# BLDC-sensorless-prototip-1.net
KiCad netlist of a schematic drawn in Altium Designer
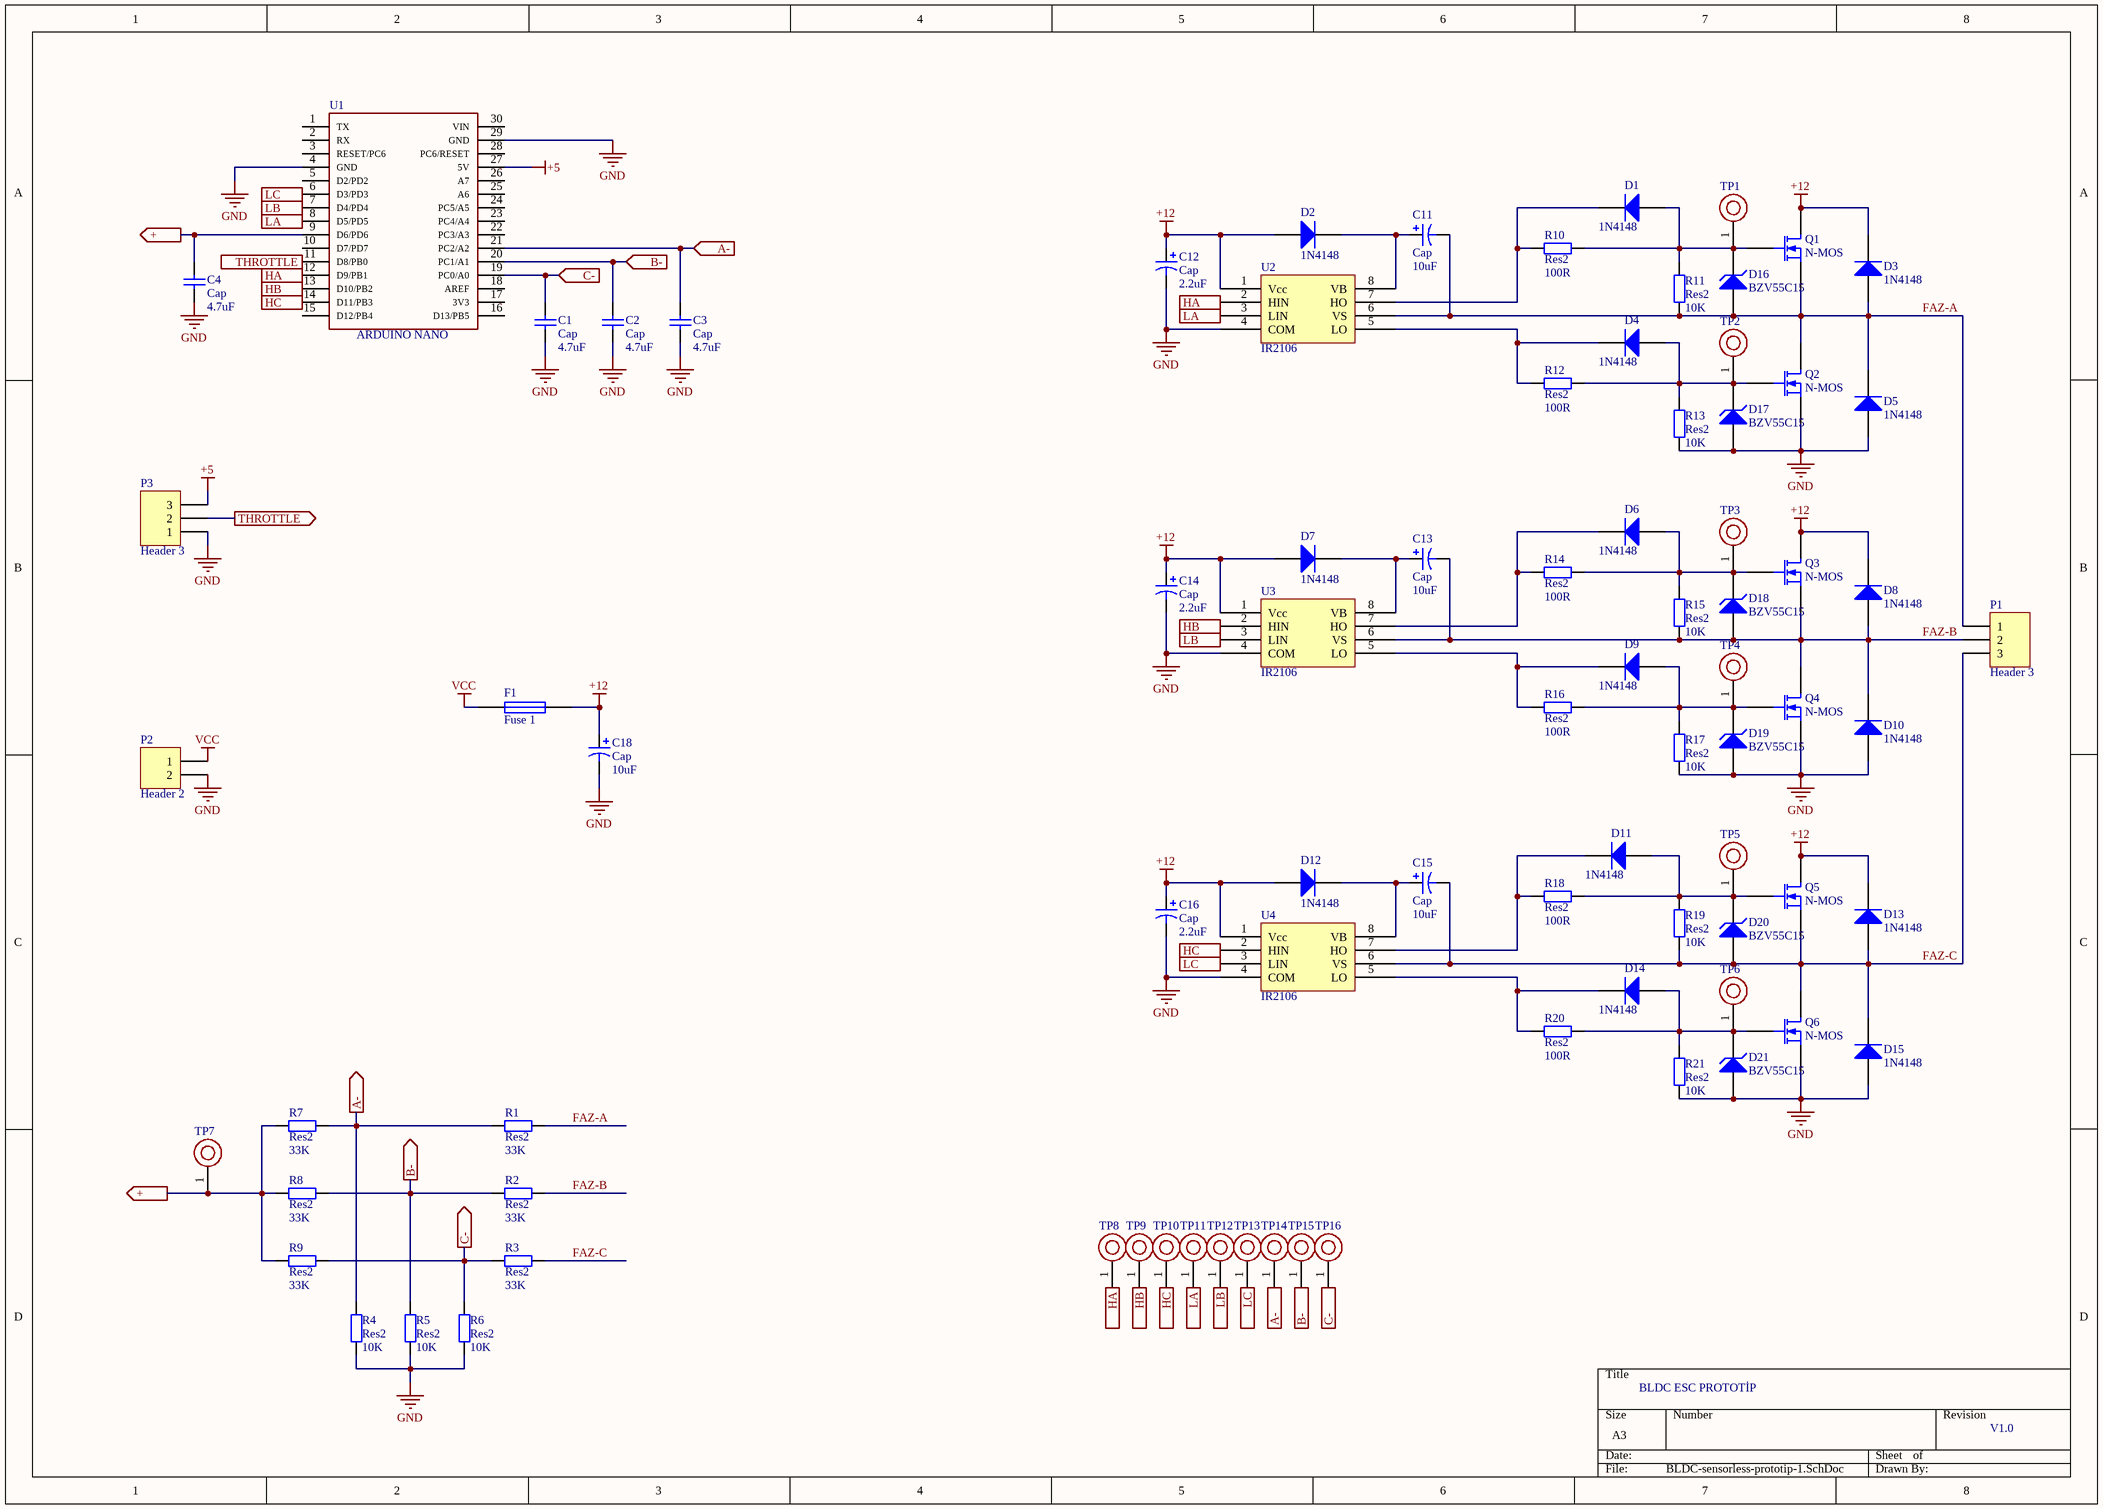
[diagram p0: BLDC-sensorless-prototip-1.SchDoc]

(export (version "E")
  (design (tool "Eeschema 10.0.6"))
  (components
    (comp (ref "C1")
      (value "Cap")
      (footprint "CAP-1206")
      (description "Capacitor")
      (fields (field (name "ALTIUM_VALUE") "4.7uF") (field (name "PUBLISHER") "Altium Limited"))
      (libsource (lib "Miscellaneous Devices") (part "Cap"))
    )
    (comp (ref "C2")
      (value "Cap")
      (footprint "CAP-1206")
      (description "Capacitor")
      (fields (field (name "ALTIUM_VALUE") "4.7uF") (field (name "PUBLISHER") "Altium Limited"))
      (libsource (lib "Miscellaneous Devices") (part "Cap"))
    )
    (comp (ref "C3")
      (value "Cap")
      (footprint "CAP-1206")
      (description "Capacitor")
      (fields (field (name "ALTIUM_VALUE") "4.7uF") (field (name "PUBLISHER") "Altium Limited"))
      (libsource (lib "Miscellaneous Devices") (part "Cap"))
    )
    (comp (ref "C4")
      (value "Cap")
      (footprint "CAP-1206")
      (description "Capacitor")
      (fields (field (name "ALTIUM_VALUE") "4.7uF") (field (name "PUBLISHER") "Altium Limited"))
      (libsource (lib "Miscellaneous Devices") (part "Cap"))
    )
    (comp (ref "C11")
      (value "Cap")
      (footprint "CAP-ELEC-2.54MM")
      (description "Polarized Capacitor (Radial)")
      (fields (field (name "ALTIUM_VALUE") "10uF") (field (name "PUBLISHER") "Altium Limited"))
      (libsource (lib "Miscellaneous Devices") (part "Cap Pol1"))
    )
    (comp (ref "C12")
      (value "Cap")
      (footprint "CAP-ELEC-2.54MM")
      (description "Polarized Capacitor (Radial)")
      (fields (field (name "ALTIUM_VALUE") "2.2uF") (field (name "PUBLISHER") "Altium Limited"))
      (libsource (lib "Miscellaneous Devices") (part "Cap Pol1"))
    )
    (comp (ref "C13")
      (value "Cap")
      (footprint "CAP-ELEC-2.54MM")
      (description "Polarized Capacitor (Radial)")
      (fields (field (name "ALTIUM_VALUE") "10uF") (field (name "PUBLISHER") "Altium Limited"))
      (libsource (lib "Miscellaneous Devices") (part "Cap Pol1"))
    )
    (comp (ref "C14")
      (value "Cap")
      (footprint "CAP-ELEC-2.54MM")
      (description "Polarized Capacitor (Radial)")
      (fields (field (name "ALTIUM_VALUE") "2.2uF") (field (name "PUBLISHER") "Altium Limited"))
      (libsource (lib "Miscellaneous Devices") (part "Cap Pol1"))
    )
    (comp (ref "C15")
      (value "Cap")
      (footprint "CAP-ELEC-2.54MM")
      (description "Polarized Capacitor (Radial)")
      (fields (field (name "ALTIUM_VALUE") "10uF") (field (name "PUBLISHER") "Altium Limited"))
      (libsource (lib "Miscellaneous Devices") (part "Cap Pol1"))
    )
    (comp (ref "C16")
      (value "Cap")
      (footprint "CAP-ELEC-2.54MM")
      (description "Polarized Capacitor (Radial)")
      (fields (field (name "ALTIUM_VALUE") "2.2uF") (field (name "PUBLISHER") "Altium Limited"))
      (libsource (lib "Miscellaneous Devices") (part "Cap Pol1"))
    )
    (comp (ref "C18")
      (value "Cap")
      (footprint "CAP-ELEC-2.54MM")
      (description "Polarized Capacitor (Radial)")
      (fields (field (name "ALTIUM_VALUE") "10uF") (field (name "PUBLISHER") "Altium Limited"))
      (libsource (lib "Miscellaneous Devices") (part "Cap Pol1"))
    )
    (comp (ref "D1")
      (value "1N4148")
      (footprint "DO-213-minielf (SOD80)")
      (description "High Conductance Fast Diode")
      (fields (field (name "PUBLISHER") "Altium Limited"))
      (libsource (lib "Miscellaneous Devices") (part "Diode 1N4148"))
    )
    (comp (ref "D2")
      (value "1N4148")
      (footprint "DO-213-minielf (SOD80)")
      (description "High Conductance Fast Diode")
      (fields (field (name "PUBLISHER") "Altium Limited"))
      (libsource (lib "Miscellaneous Devices") (part "Diode 1N4148"))
    )
    (comp (ref "D3")
      (value "1N4148")
      (footprint "DO-213-minielf (SOD80)")
      (description "Default Diode")
      (fields (field (name "PUBLISHER") "Altium Limited"))
      (libsource (lib "Miscellaneous Devices") (part "Diode"))
    )
    (comp (ref "D4")
      (value "1N4148")
      (footprint "DO-213-minielf (SOD80)")
      (description "High Conductance Fast Diode")
      (fields (field (name "PUBLISHER") "Altium Limited"))
      (libsource (lib "Miscellaneous Devices") (part "Diode 1N4148"))
    )
    (comp (ref "D5")
      (value "1N4148")
      (footprint "DO-213-minielf (SOD80)")
      (description "Default Diode")
      (fields (field (name "PUBLISHER") "Altium Limited"))
      (libsource (lib "Miscellaneous Devices") (part "Diode"))
    )
    (comp (ref "D6")
      (value "1N4148")
      (footprint "DO-213-minielf (SOD80)")
      (description "High Conductance Fast Diode")
      (fields (field (name "PUBLISHER") "Altium Limited"))
      (libsource (lib "Miscellaneous Devices") (part "Diode 1N4148"))
    )
    (comp (ref "D7")
      (value "1N4148")
      (footprint "DO-213-minielf (SOD80)")
      (description "High Conductance Fast Diode")
      (fields (field (name "PUBLISHER") "Altium Limited"))
      (libsource (lib "Miscellaneous Devices") (part "Diode 1N4148"))
    )
    (comp (ref "D8")
      (value "1N4148")
      (footprint "DO-213-minielf (SOD80)")
      (description "Default Diode")
      (fields (field (name "PUBLISHER") "Altium Limited"))
      (libsource (lib "Miscellaneous Devices") (part "Diode"))
    )
    (comp (ref "D9")
      (value "1N4148")
      (footprint "DO-213-minielf (SOD80)")
      (description "High Conductance Fast Diode")
      (fields (field (name "PUBLISHER") "Altium Limited"))
      (libsource (lib "Miscellaneous Devices") (part "Diode 1N4148"))
    )
    (comp (ref "D10")
      (value "1N4148")
      (footprint "DO-213-minielf (SOD80)")
      (description "Default Diode")
      (fields (field (name "PUBLISHER") "Altium Limited"))
      (libsource (lib "Miscellaneous Devices") (part "Diode"))
    )
    (comp (ref "D11")
      (value "1N4148")
      (footprint "DO-213-minielf (SOD80)")
      (description "High Conductance Fast Diode")
      (fields (field (name "PUBLISHER") "Altium Limited"))
      (libsource (lib "Miscellaneous Devices") (part "Diode 1N4148"))
    )
    (comp (ref "D12")
      (value "1N4148")
      (footprint "DO-213-minielf (SOD80)")
      (description "High Conductance Fast Diode")
      (fields (field (name "PUBLISHER") "Altium Limited"))
      (libsource (lib "Miscellaneous Devices") (part "Diode 1N4148"))
    )
    (comp (ref "D13")
      (value "1N4148")
      (footprint "DO-213-minielf (SOD80)")
      (description "Default Diode")
      (fields (field (name "PUBLISHER") "Altium Limited"))
      (libsource (lib "Miscellaneous Devices") (part "Diode"))
    )
    (comp (ref "D14")
      (value "1N4148")
      (footprint "DO-213-minielf (SOD80)")
      (description "High Conductance Fast Diode")
      (fields (field (name "PUBLISHER") "Altium Limited"))
      (libsource (lib "Miscellaneous Devices") (part "Diode 1N4148"))
    )
    (comp (ref "D15")
      (value "1N4148")
      (footprint "DO-213-minielf (SOD80)")
      (description "Default Diode")
      (fields (field (name "PUBLISHER") "Altium Limited"))
      (libsource (lib "Miscellaneous Devices") (part "Diode"))
    )
    (comp (ref "D16")
      (value "BZV55C15")
      (footprint "DO-213-minielf (SOD80)")
      (description "Zener Diode")
      (fields (field (name "PUBLISHER") "Altium Limited"))
      (libsource (lib "Miscellaneous Devices") (part "D Zener"))
    )
    (comp (ref "D17")
      (value "BZV55C15")
      (footprint "DO-213-minielf (SOD80)")
      (description "Zener Diode")
      (fields (field (name "PUBLISHER") "Altium Limited"))
      (libsource (lib "Miscellaneous Devices") (part "D Zener"))
    )
    (comp (ref "D18")
      (value "BZV55C15")
      (footprint "DO-213-minielf (SOD80)")
      (description "Zener Diode")
      (fields (field (name "PUBLISHER") "Altium Limited"))
      (libsource (lib "Miscellaneous Devices") (part "D Zener"))
    )
    (comp (ref "D19")
      (value "BZV55C15")
      (footprint "DO-213-minielf (SOD80)")
      (description "Zener Diode")
      (fields (field (name "PUBLISHER") "Altium Limited"))
      (libsource (lib "Miscellaneous Devices") (part "D Zener"))
    )
    (comp (ref "D20")
      (value "BZV55C15")
      (footprint "DO-213-minielf (SOD80)")
      (description "Zener Diode")
      (fields (field (name "PUBLISHER") "Altium Limited"))
      (libsource (lib "Miscellaneous Devices") (part "D Zener"))
    )
    (comp (ref "D21")
      (value "BZV55C15")
      (footprint "DO-213-minielf (SOD80)")
      (description "Zener Diode")
      (fields (field (name "PUBLISHER") "Altium Limited"))
      (libsource (lib "Miscellaneous Devices") (part "D Zener"))
    )
    (comp (ref "F1")
      (value "Fuse 1")
      (footprint "FUSE HOLDER")
      (description "Fuse")
      (fields (field (name "PUBLISHER") "Altium Limited"))
      (libsource (lib "Miscellaneous Devices") (part "Fuse 1"))
    )
    (comp (ref "P1")
      (value "Header 3")
      (footprint "3.81MM KLEMENS X3")
      (description "Header, 3-Pin")
      (fields (field (name "PUBLISHER") "Altium Limited"))
      (libsource (lib "") (part "Header 3_1"))
    )
    (comp (ref "P2")
      (value "Header 2")
      (footprint "5.08MM KLEMENS X2")
      (description "Header, 2-Pin")
      (fields (field (name "PUBLISHER") "Altium Limited"))
      (libsource (lib "Miscellaneous Connectors") (part "Header 2"))
    )
    (comp (ref "P3")
      (value "Header 3")
      (footprint "2.54MM ERKEK HEADER X3")
      (description "Header, 3-Pin")
      (fields (field (name "PUBLISHER") "Altium Limited"))
      (libsource (lib "Miscellaneous Connectors") (part "Header 3"))
    )
    (comp (ref "Q1")
      (value "N-MOS")
      (footprint "TO-252-3")
      (description "N-Channel MOSFET")
      (fields (field (name "PUBLISHER") "Altium Limited"))
      (libsource (lib "Miscellaneous Devices") (part "MOSFET-N"))
    )
    (comp (ref "Q2")
      (value "N-MOS")
      (footprint "TO-252-3")
      (description "N-Channel MOSFET")
      (fields (field (name "PUBLISHER") "Altium Limited"))
      (libsource (lib "Miscellaneous Devices") (part "MOSFET-N"))
    )
    (comp (ref "Q3")
      (value "N-MOS")
      (footprint "TO-252-3")
      (description "N-Channel MOSFET")
      (fields (field (name "PUBLISHER") "Altium Limited"))
      (libsource (lib "Miscellaneous Devices") (part "MOSFET-N"))
    )
    (comp (ref "Q4")
      (value "N-MOS")
      (footprint "TO-252-3")
      (description "N-Channel MOSFET")
      (fields (field (name "PUBLISHER") "Altium Limited"))
      (libsource (lib "Miscellaneous Devices") (part "MOSFET-N"))
    )
    (comp (ref "Q5")
      (value "N-MOS")
      (footprint "TO-252-3")
      (description "N-Channel MOSFET")
      (fields (field (name "PUBLISHER") "Altium Limited"))
      (libsource (lib "Miscellaneous Devices") (part "MOSFET-N"))
    )
    (comp (ref "Q6")
      (value "N-MOS")
      (footprint "TO-252-3")
      (description "N-Channel MOSFET")
      (fields (field (name "PUBLISHER") "Altium Limited"))
      (libsource (lib "Miscellaneous Devices") (part "MOSFET-N"))
    )
    (comp (ref "R1")
      (value "Res2")
      (footprint "RES-1206")
      (description "Resistor")
      (fields (field (name "ALTIUM_VALUE") "33K") (field (name "PUBLISHER") "Altium Limited"))
      (libsource (lib "Miscellaneous Devices") (part "Res2"))
    )
    (comp (ref "R2")
      (value "Res2")
      (footprint "RES-1206")
      (description "Resistor")
      (fields (field (name "ALTIUM_VALUE") "33K") (field (name "PUBLISHER") "Altium Limited"))
      (libsource (lib "Miscellaneous Devices") (part "Res2"))
    )
    (comp (ref "R3")
      (value "Res2")
      (footprint "RES-1206")
      (description "Resistor")
      (fields (field (name "ALTIUM_VALUE") "33K") (field (name "PUBLISHER") "Altium Limited"))
      (libsource (lib "Miscellaneous Devices") (part "Res2"))
    )
    (comp (ref "R4")
      (value "Res2")
      (footprint "RES-1206")
      (description "Resistor")
      (fields (field (name "ALTIUM_VALUE") "10K") (field (name "PUBLISHER") "Altium Limited"))
      (libsource (lib "") (part "Res2_1"))
    )
    (comp (ref "R5")
      (value "Res2")
      (footprint "RES-1206")
      (description "Resistor")
      (fields (field (name "ALTIUM_VALUE") "10K") (field (name "PUBLISHER") "Altium Limited"))
      (libsource (lib "") (part "Res2_1"))
    )
    (comp (ref "R6")
      (value "Res2")
      (footprint "RES-1206")
      (description "Resistor")
      (fields (field (name "ALTIUM_VALUE") "10K") (field (name "PUBLISHER") "Altium Limited"))
      (libsource (lib "") (part "Res2_1"))
    )
    (comp (ref "R7")
      (value "Res2")
      (footprint "RES-1206")
      (description "Resistor")
      (fields (field (name "ALTIUM_VALUE") "33K") (field (name "PUBLISHER") "Altium Limited"))
      (libsource (lib "Miscellaneous Devices") (part "Res2"))
    )
    (comp (ref "R8")
      (value "Res2")
      (footprint "RES-1206")
      (description "Resistor")
      (fields (field (name "ALTIUM_VALUE") "33K") (field (name "PUBLISHER") "Altium Limited"))
      (libsource (lib "Miscellaneous Devices") (part "Res2"))
    )
    (comp (ref "R9")
      (value "Res2")
      (footprint "RES-1206")
      (description "Resistor")
      (fields (field (name "ALTIUM_VALUE") "33K") (field (name "PUBLISHER") "Altium Limited"))
      (libsource (lib "Miscellaneous Devices") (part "Res2"))
    )
    (comp (ref "R10")
      (value "Res2")
      (footprint "RES-1206")
      (description "Resistor")
      (fields (field (name "ALTIUM_VALUE") "100R") (field (name "PUBLISHER") "Altium Limited"))
      (libsource (lib "Miscellaneous Devices") (part "Res2"))
    )
    (comp (ref "R11")
      (value "Res2")
      (footprint "RES-1206")
      (description "Resistor")
      (fields (field (name "ALTIUM_VALUE") "10K") (field (name "PUBLISHER") "Altium Limited"))
      (libsource (lib "") (part "Res2_1"))
    )
    (comp (ref "R12")
      (value "Res2")
      (footprint "RES-1206")
      (description "Resistor")
      (fields (field (name "ALTIUM_VALUE") "100R") (field (name "PUBLISHER") "Altium Limited"))
      (libsource (lib "Miscellaneous Devices") (part "Res2"))
    )
    (comp (ref "R13")
      (value "Res2")
      (footprint "RES-1206")
      (description "Resistor")
      (fields (field (name "ALTIUM_VALUE") "10K") (field (name "PUBLISHER") "Altium Limited"))
      (libsource (lib "") (part "Res2_1"))
    )
    (comp (ref "R14")
      (value "Res2")
      (footprint "RES-1206")
      (description "Resistor")
      (fields (field (name "ALTIUM_VALUE") "100R") (field (name "PUBLISHER") "Altium Limited"))
      (libsource (lib "Miscellaneous Devices") (part "Res2"))
    )
    (comp (ref "R15")
      (value "Res2")
      (footprint "RES-1206")
      (description "Resistor")
      (fields (field (name "ALTIUM_VALUE") "10K") (field (name "PUBLISHER") "Altium Limited"))
      (libsource (lib "") (part "Res2_1"))
    )
    (comp (ref "R16")
      (value "Res2")
      (footprint "RES-1206")
      (description "Resistor")
      (fields (field (name "ALTIUM_VALUE") "100R") (field (name "PUBLISHER") "Altium Limited"))
      (libsource (lib "Miscellaneous Devices") (part "Res2"))
    )
    (comp (ref "R17")
      (value "Res2")
      (footprint "RES-1206")
      (description "Resistor")
      (fields (field (name "ALTIUM_VALUE") "10K") (field (name "PUBLISHER") "Altium Limited"))
      (libsource (lib "") (part "Res2_1"))
    )
    (comp (ref "R18")
      (value "Res2")
      (footprint "RES-1206")
      (description "Resistor")
      (fields (field (name "ALTIUM_VALUE") "100R") (field (name "PUBLISHER") "Altium Limited"))
      (libsource (lib "Miscellaneous Devices") (part "Res2"))
    )
    (comp (ref "R19")
      (value "Res2")
      (footprint "RES-1206")
      (description "Resistor")
      (fields (field (name "ALTIUM_VALUE") "10K") (field (name "PUBLISHER") "Altium Limited"))
      (libsource (lib "") (part "Res2_1"))
    )
    (comp (ref "R20")
      (value "Res2")
      (footprint "RES-1206")
      (description "Resistor")
      (fields (field (name "ALTIUM_VALUE") "100R") (field (name "PUBLISHER") "Altium Limited"))
      (libsource (lib "Miscellaneous Devices") (part "Res2"))
    )
    (comp (ref "R21")
      (value "Res2")
      (footprint "RES-1206")
      (description "Resistor")
      (fields (field (name "ALTIUM_VALUE") "10K") (field (name "PUBLISHER") "Altium Limited"))
      (libsource (lib "") (part "Res2_1"))
    )
    (comp (ref "TP1")
      (value "TEST POINT")
      (footprint "Test Point")
      (libsource (lib "Sematik Kutuphane") (part "TEST POINT"))
    )
    (comp (ref "TP2")
      (value "TEST POINT")
      (footprint "Test Point")
      (libsource (lib "Sematik Kutuphane") (part "TEST POINT"))
    )
    (comp (ref "TP3")
      (value "TEST POINT")
      (footprint "Test Point")
      (libsource (lib "Sematik Kutuphane") (part "TEST POINT"))
    )
    (comp (ref "TP4")
      (value "TEST POINT")
      (footprint "Test Point")
      (libsource (lib "Sematik Kutuphane") (part "TEST POINT"))
    )
    (comp (ref "TP5")
      (value "TEST POINT")
      (footprint "Test Point")
      (libsource (lib "Sematik Kutuphane") (part "TEST POINT"))
    )
    (comp (ref "TP6")
      (value "TEST POINT")
      (footprint "Test Point")
      (libsource (lib "Sematik Kutuphane") (part "TEST POINT"))
    )
    (comp (ref "TP7")
      (value "TEST POINT")
      (footprint "Test Point")
      (libsource (lib "Sematik Kutuphane") (part "TEST POINT"))
    )
    (comp (ref "TP8")
      (value "TEST POINT")
      (footprint "Test Point")
      (libsource (lib "Sematik Kutuphane") (part "TEST POINT"))
    )
    (comp (ref "TP9")
      (value "TEST POINT")
      (footprint "Test Point")
      (libsource (lib "Sematik Kutuphane") (part "TEST POINT"))
    )
    (comp (ref "TP10")
      (value "TEST POINT")
      (footprint "Test Point")
      (libsource (lib "Sematik Kutuphane") (part "TEST POINT"))
    )
    (comp (ref "TP11")
      (value "TEST POINT")
      (footprint "Test Point")
      (libsource (lib "Sematik Kutuphane") (part "TEST POINT"))
    )
    (comp (ref "TP12")
      (value "TEST POINT")
      (footprint "Test Point")
      (libsource (lib "Sematik Kutuphane") (part "TEST POINT"))
    )
    (comp (ref "TP13")
      (value "TEST POINT")
      (footprint "Test Point")
      (libsource (lib "Sematik Kutuphane") (part "TEST POINT"))
    )
    (comp (ref "TP14")
      (value "TEST POINT")
      (footprint "Test Point")
      (libsource (lib "Sematik Kutuphane") (part "TEST POINT"))
    )
    (comp (ref "TP15")
      (value "TEST POINT")
      (footprint "Test Point")
      (libsource (lib "Sematik Kutuphane") (part "TEST POINT"))
    )
    (comp (ref "TP16")
      (value "TEST POINT")
      (footprint "Test Point")
      (libsource (lib "Sematik Kutuphane") (part "TEST POINT"))
    )
    (comp (ref "U1")
      (value "ARDUINO NANO")
      (footprint "ARDUINO NANO")
      (libsource (lib "Sematik Kutuphane") (part "ARDUINO NANO"))
    )
    (comp (ref "U2")
      (value "IR2106")
      (footprint "DIP-8")
      (libsource (lib "Sematik Kutuphane") (part "IR2106"))
    )
    (comp (ref "U3")
      (value "IR2106")
      (footprint "DIP-8")
      (libsource (lib "Sematik Kutuphane") (part "IR2106"))
    )
    (comp (ref "U4")
      (value "IR2106")
      (footprint "DIP-8")
      (libsource (lib "Sematik Kutuphane") (part "IR2106"))
    )
  )
  (nets
    (net (code "1") (name "+5") (class "Default")
      (node (ref "P3") (pin "3") (pinfunction "3_3") (pintype "passive"))
      (node (ref "U1") (pin "27") (pinfunction "5V_27") (pintype "passive"))
    )
    (net (code "2") (name "+12") (class "Default")
      (node (ref "C12") (pin "1") (pinfunction "1_1") (pintype "passive"))
      (node (ref "C14") (pin "1") (pinfunction "1_1") (pintype "passive"))
      (node (ref "C16") (pin "1") (pinfunction "1_1") (pintype "passive"))
      (node (ref "C18") (pin "1") (pinfunction "1_1") (pintype "passive"))
      (node (ref "D12") (pin "1") (pinfunction "A_1") (pintype "passive"))
      (node (ref "D13") (pin "2") (pinfunction "K_2") (pintype "passive"))
      (node (ref "D2") (pin "1") (pinfunction "A_1") (pintype "passive"))
      (node (ref "D3") (pin "2") (pinfunction "K_2") (pintype "passive"))
      (node (ref "D7") (pin "1") (pinfunction "A_1") (pintype "passive"))
      (node (ref "D8") (pin "2") (pinfunction "K_2") (pintype "passive"))
      (node (ref "F1") (pin "2") (pinfunction "2_2") (pintype "passive"))
      (node (ref "Q1") (pin "2") (pinfunction "D_2") (pintype "passive"))
      (node (ref "Q3") (pin "2") (pinfunction "D_2") (pintype "passive"))
      (node (ref "Q5") (pin "2") (pinfunction "D_2") (pintype "passive"))
      (node (ref "U2") (pin "1") (pinfunction "Vcc_1") (pintype "passive"))
      (node (ref "U3") (pin "1") (pinfunction "Vcc_1") (pintype "passive"))
      (node (ref "U4") (pin "1") (pinfunction "Vcc_1") (pintype "passive"))
    )
    (net (code "3") (name "/+") (class "Default")
      (node (ref "C4") (pin "2") (pinfunction "2_2") (pintype "passive"))
      (node (ref "R7") (pin "1") (pinfunction "1_1") (pintype "passive"))
      (node (ref "R8") (pin "1") (pinfunction "1_1") (pintype "passive"))
      (node (ref "R9") (pin "1") (pinfunction "1_1") (pintype "passive"))
      (node (ref "TP7") (pin "1") (pintype "passive"))
      (node (ref "U1") (pin "9") (pinfunction "D6/PD6_9") (pintype "passive"))
    )
    (net (code "4") (name "/A-") (class "Default")
      (node (ref "C3") (pin "2") (pinfunction "2_2") (pintype "passive"))
      (node (ref "R1") (pin "1") (pinfunction "1_1") (pintype "passive"))
      (node (ref "R4") (pin "2") (pinfunction "2_2") (pintype "passive"))
      (node (ref "R7") (pin "2") (pinfunction "2_2") (pintype "passive"))
      (node (ref "TP14") (pin "1") (pintype "passive"))
      (node (ref "U1") (pin "21") (pinfunction "PC2/A2_21") (pintype "passive"))
    )
    (net (code "5") (name "/B-") (class "Default")
      (node (ref "C2") (pin "2") (pinfunction "2_2") (pintype "passive"))
      (node (ref "R2") (pin "1") (pinfunction "1_1") (pintype "passive"))
      (node (ref "R5") (pin "2") (pinfunction "2_2") (pintype "passive"))
      (node (ref "R8") (pin "2") (pinfunction "2_2") (pintype "passive"))
      (node (ref "TP15") (pin "1") (pintype "passive"))
      (node (ref "U1") (pin "20") (pinfunction "PC1/A1_20") (pintype "passive"))
    )
    (net (code "6") (name "/C-") (class "Default")
      (node (ref "C1") (pin "2") (pinfunction "2_2") (pintype "passive"))
      (node (ref "R3") (pin "1") (pinfunction "1_1") (pintype "passive"))
      (node (ref "R6") (pin "2") (pinfunction "2_2") (pintype "passive"))
      (node (ref "R9") (pin "2") (pinfunction "2_2") (pintype "passive"))
      (node (ref "TP16") (pin "1") (pintype "passive"))
      (node (ref "U1") (pin "19") (pinfunction "PC0/A0_19") (pintype "passive"))
    )
    (net (code "7") (name "/FAZ-A") (class "Default")
      (node (ref "C11") (pin "2") (pinfunction "2_2") (pintype "passive"))
      (node (ref "D16") (pin "1") (pinfunction "A_1") (pintype "passive"))
      (node (ref "D3") (pin "1") (pinfunction "A_1") (pintype "passive"))
      (node (ref "D5") (pin "2") (pinfunction "K_2") (pintype "passive"))
      (node (ref "P1") (pin "1") (pinfunction "1_1") (pintype "passive"))
      (node (ref "Q1") (pin "3") (pinfunction "S_3") (pintype "passive"))
      (node (ref "Q2") (pin "2") (pinfunction "D_2") (pintype "passive"))
      (node (ref "R1") (pin "2") (pinfunction "2_2") (pintype "passive"))
      (node (ref "R11") (pin "1") (pinfunction "1_1") (pintype "passive"))
      (node (ref "U2") (pin "6") (pinfunction "VS_6") (pintype "passive"))
    )
    (net (code "8") (name "/FAZ-B") (class "Default")
      (node (ref "C13") (pin "2") (pinfunction "2_2") (pintype "passive"))
      (node (ref "D10") (pin "2") (pinfunction "K_2") (pintype "passive"))
      (node (ref "D18") (pin "1") (pinfunction "A_1") (pintype "passive"))
      (node (ref "D8") (pin "1") (pinfunction "A_1") (pintype "passive"))
      (node (ref "P1") (pin "2") (pinfunction "2_2") (pintype "passive"))
      (node (ref "Q3") (pin "3") (pinfunction "S_3") (pintype "passive"))
      (node (ref "Q4") (pin "2") (pinfunction "D_2") (pintype "passive"))
      (node (ref "R15") (pin "1") (pinfunction "1_1") (pintype "passive"))
      (node (ref "R2") (pin "2") (pinfunction "2_2") (pintype "passive"))
      (node (ref "U3") (pin "6") (pinfunction "VS_6") (pintype "passive"))
    )
    (net (code "9") (name "/FAZ-C") (class "Default")
      (node (ref "C15") (pin "2") (pinfunction "2_2") (pintype "passive"))
      (node (ref "D13") (pin "1") (pinfunction "A_1") (pintype "passive"))
      (node (ref "D15") (pin "2") (pinfunction "K_2") (pintype "passive"))
      (node (ref "D20") (pin "1") (pinfunction "A_1") (pintype "passive"))
      (node (ref "P1") (pin "3") (pinfunction "3_3") (pintype "passive"))
      (node (ref "Q5") (pin "3") (pinfunction "S_3") (pintype "passive"))
      (node (ref "Q6") (pin "2") (pinfunction "D_2") (pintype "passive"))
      (node (ref "R19") (pin "1") (pinfunction "1_1") (pintype "passive"))
      (node (ref "R3") (pin "2") (pinfunction "2_2") (pintype "passive"))
      (node (ref "U4") (pin "6") (pinfunction "VS_6") (pintype "passive"))
    )
    (net (code "10") (name "/HA") (class "Default")
      (node (ref "TP8") (pin "1") (pintype "passive"))
      (node (ref "U1") (pin "12") (pinfunction "D9/PB1_12") (pintype "passive"))
      (node (ref "U2") (pin "2") (pinfunction "HIN_2") (pintype "passive"))
    )
    (net (code "11") (name "/HB") (class "Default")
      (node (ref "TP9") (pin "1") (pintype "passive"))
      (node (ref "U1") (pin "13") (pinfunction "D10/PB2_13") (pintype "passive"))
      (node (ref "U3") (pin "2") (pinfunction "HIN_2") (pintype "passive"))
    )
    (net (code "12") (name "/HC") (class "Default")
      (node (ref "TP10") (pin "1") (pintype "passive"))
      (node (ref "U1") (pin "14") (pinfunction "D11/PB3_14") (pintype "passive"))
      (node (ref "U4") (pin "2") (pinfunction "HIN_2") (pintype "passive"))
    )
    (net (code "13") (name "/LA") (class "Default")
      (node (ref "TP11") (pin "1") (pintype "passive"))
      (node (ref "U1") (pin "8") (pinfunction "D5/PD5_8") (pintype "passive"))
      (node (ref "U2") (pin "3") (pinfunction "LIN_3") (pintype "passive"))
    )
    (net (code "14") (name "/LB") (class "Default")
      (node (ref "TP12") (pin "1") (pintype "passive"))
      (node (ref "U1") (pin "7") (pinfunction "D4/PD4_7") (pintype "passive"))
      (node (ref "U3") (pin "3") (pinfunction "LIN_3") (pintype "passive"))
    )
    (net (code "15") (name "/LC") (class "Default")
      (node (ref "TP13") (pin "1") (pintype "passive"))
      (node (ref "U1") (pin "6") (pinfunction "D3/PD3_6") (pintype "passive"))
      (node (ref "U4") (pin "3") (pinfunction "LIN_3") (pintype "passive"))
    )
    (net (code "16") (name "/THROTTLE") (class "Default")
      (node (ref "P3") (pin "2") (pinfunction "2_2") (pintype "passive"))
      (node (ref "U1") (pin "11") (pinfunction "D8/PB0_11") (pintype "passive"))
    )
    (net (code "17") (name "GND") (class "Default")
      (node (ref "C1") (pin "1") (pinfunction "1_1") (pintype "passive"))
      (node (ref "C12") (pin "2") (pinfunction "2_2") (pintype "passive"))
      (node (ref "C14") (pin "2") (pinfunction "2_2") (pintype "passive"))
      (node (ref "C16") (pin "2") (pinfunction "2_2") (pintype "passive"))
      (node (ref "C18") (pin "2") (pinfunction "2_2") (pintype "passive"))
      (node (ref "C2") (pin "1") (pinfunction "1_1") (pintype "passive"))
      (node (ref "C3") (pin "1") (pinfunction "1_1") (pintype "passive"))
      (node (ref "C4") (pin "1") (pinfunction "1_1") (pintype "passive"))
      (node (ref "D10") (pin "1") (pinfunction "A_1") (pintype "passive"))
      (node (ref "D15") (pin "1") (pinfunction "A_1") (pintype "passive"))
      (node (ref "D17") (pin "1") (pinfunction "A_1") (pintype "passive"))
      (node (ref "D19") (pin "1") (pinfunction "A_1") (pintype "passive"))
      (node (ref "D21") (pin "1") (pinfunction "A_1") (pintype "passive"))
      (node (ref "D5") (pin "1") (pinfunction "A_1") (pintype "passive"))
      (node (ref "P2") (pin "2") (pinfunction "2_2") (pintype "passive"))
      (node (ref "P3") (pin "1") (pinfunction "1_1") (pintype "passive"))
      (node (ref "Q2") (pin "3") (pinfunction "S_3") (pintype "passive"))
      (node (ref "Q4") (pin "3") (pinfunction "S_3") (pintype "passive"))
      (node (ref "Q6") (pin "3") (pinfunction "S_3") (pintype "passive"))
      (node (ref "R13") (pin "1") (pinfunction "1_1") (pintype "passive"))
      (node (ref "R17") (pin "1") (pinfunction "1_1") (pintype "passive"))
      (node (ref "R21") (pin "1") (pinfunction "1_1") (pintype "passive"))
      (node (ref "R4") (pin "1") (pinfunction "1_1") (pintype "passive"))
      (node (ref "R5") (pin "1") (pinfunction "1_1") (pintype "passive"))
      (node (ref "R6") (pin "1") (pinfunction "1_1") (pintype "passive"))
      (node (ref "U1") (pin "29") (pinfunction "GND_29") (pintype "passive"))
      (node (ref "U1") (pin "4") (pinfunction "GND_4") (pintype "passive"))
      (node (ref "U2") (pin "4") (pinfunction "COM_4") (pintype "passive"))
      (node (ref "U3") (pin "4") (pinfunction "COM_4") (pintype "passive"))
      (node (ref "U4") (pin "4") (pinfunction "COM_4") (pintype "passive"))
    )
    (net (code "18") (name "Net-(D1-A)") (class "Default")
      (node (ref "D1") (pin "1") (pinfunction "A_1") (pintype "passive"))
      (node (ref "D16") (pin "2") (pinfunction "K_2") (pintype "passive"))
      (node (ref "Q1") (pin "1") (pinfunction "G_1") (pintype "passive"))
      (node (ref "R10") (pin "2") (pinfunction "2_2") (pintype "passive"))
      (node (ref "R11") (pin "2") (pinfunction "2_2") (pintype "passive"))
      (node (ref "TP1") (pin "1") (pintype "passive"))
    )
    (net (code "19") (name "Net-(D1-K)") (class "Default")
      (node (ref "D1") (pin "2") (pinfunction "K_2") (pintype "passive"))
      (node (ref "R10") (pin "1") (pinfunction "1_1") (pintype "passive"))
      (node (ref "U2") (pin "7") (pinfunction "HO_7") (pintype "passive"))
    )
    (net (code "20") (name "Net-(D2-K)") (class "Default")
      (node (ref "C11") (pin "1") (pinfunction "1_1") (pintype "passive"))
      (node (ref "D2") (pin "2") (pinfunction "K_2") (pintype "passive"))
      (node (ref "U2") (pin "8") (pinfunction "VB_8") (pintype "passive"))
    )
    (net (code "21") (name "Net-(D4-K)") (class "Default")
      (node (ref "D4") (pin "2") (pinfunction "K_2") (pintype "passive"))
      (node (ref "R12") (pin "1") (pinfunction "1_1") (pintype "passive"))
      (node (ref "U2") (pin "5") (pinfunction "LO_5") (pintype "passive"))
    )
    (net (code "22") (name "Net-(D6-K)") (class "Default")
      (node (ref "D6") (pin "2") (pinfunction "K_2") (pintype "passive"))
      (node (ref "R14") (pin "1") (pinfunction "1_1") (pintype "passive"))
      (node (ref "U3") (pin "7") (pinfunction "HO_7") (pintype "passive"))
    )
    (net (code "23") (name "Net-(D7-K)") (class "Default")
      (node (ref "C13") (pin "1") (pinfunction "1_1") (pintype "passive"))
      (node (ref "D7") (pin "2") (pinfunction "K_2") (pintype "passive"))
      (node (ref "U3") (pin "8") (pinfunction "VB_8") (pintype "passive"))
    )
    (net (code "24") (name "Net-(D9-K)") (class "Default")
      (node (ref "D9") (pin "2") (pinfunction "K_2") (pintype "passive"))
      (node (ref "R16") (pin "1") (pinfunction "1_1") (pintype "passive"))
      (node (ref "U3") (pin "5") (pinfunction "LO_5") (pintype "passive"))
    )
    (net (code "25") (name "Net-(D11-A)") (class "Default")
      (node (ref "D11") (pin "1") (pinfunction "A_1") (pintype "passive"))
      (node (ref "D20") (pin "2") (pinfunction "K_2") (pintype "passive"))
      (node (ref "Q5") (pin "1") (pinfunction "G_1") (pintype "passive"))
      (node (ref "R18") (pin "2") (pinfunction "2_2") (pintype "passive"))
      (node (ref "R19") (pin "2") (pinfunction "2_2") (pintype "passive"))
      (node (ref "TP5") (pin "1") (pintype "passive"))
    )
    (net (code "26") (name "Net-(D11-K)") (class "Default")
      (node (ref "D11") (pin "2") (pinfunction "K_2") (pintype "passive"))
      (node (ref "R18") (pin "1") (pinfunction "1_1") (pintype "passive"))
      (node (ref "U4") (pin "7") (pinfunction "HO_7") (pintype "passive"))
    )
    (net (code "27") (name "Net-(D12-K)") (class "Default")
      (node (ref "C15") (pin "1") (pinfunction "1_1") (pintype "passive"))
      (node (ref "D12") (pin "2") (pinfunction "K_2") (pintype "passive"))
      (node (ref "U4") (pin "8") (pinfunction "VB_8") (pintype "passive"))
    )
    (net (code "28") (name "Net-(D14-A)") (class "Default")
      (node (ref "D14") (pin "1") (pinfunction "A_1") (pintype "passive"))
      (node (ref "D21") (pin "2") (pinfunction "K_2") (pintype "passive"))
      (node (ref "Q6") (pin "1") (pinfunction "G_1") (pintype "passive"))
      (node (ref "R20") (pin "2") (pinfunction "2_2") (pintype "passive"))
      (node (ref "R21") (pin "2") (pinfunction "2_2") (pintype "passive"))
      (node (ref "TP6") (pin "1") (pintype "passive"))
    )
    (net (code "29") (name "Net-(D14-K)") (class "Default")
      (node (ref "D14") (pin "2") (pinfunction "K_2") (pintype "passive"))
      (node (ref "R20") (pin "1") (pinfunction "1_1") (pintype "passive"))
      (node (ref "U4") (pin "5") (pinfunction "LO_5") (pintype "passive"))
    )
    (net (code "30") (name "Net-(D17-K)") (class "Default")
      (node (ref "D17") (pin "2") (pinfunction "K_2") (pintype "passive"))
      (node (ref "D4") (pin "1") (pinfunction "A_1") (pintype "passive"))
      (node (ref "Q2") (pin "1") (pinfunction "G_1") (pintype "passive"))
      (node (ref "R12") (pin "2") (pinfunction "2_2") (pintype "passive"))
      (node (ref "R13") (pin "2") (pinfunction "2_2") (pintype "passive"))
      (node (ref "TP2") (pin "1") (pintype "passive"))
    )
    (net (code "31") (name "Net-(D18-K)") (class "Default")
      (node (ref "D18") (pin "2") (pinfunction "K_2") (pintype "passive"))
      (node (ref "D6") (pin "1") (pinfunction "A_1") (pintype "passive"))
      (node (ref "Q3") (pin "1") (pinfunction "G_1") (pintype "passive"))
      (node (ref "R14") (pin "2") (pinfunction "2_2") (pintype "passive"))
      (node (ref "R15") (pin "2") (pinfunction "2_2") (pintype "passive"))
      (node (ref "TP3") (pin "1") (pintype "passive"))
    )
    (net (code "32") (name "Net-(D19-K)") (class "Default")
      (node (ref "D19") (pin "2") (pinfunction "K_2") (pintype "passive"))
      (node (ref "D9") (pin "1") (pinfunction "A_1") (pintype "passive"))
      (node (ref "Q4") (pin "1") (pinfunction "G_1") (pintype "passive"))
      (node (ref "R16") (pin "2") (pinfunction "2_2") (pintype "passive"))
      (node (ref "R17") (pin "2") (pinfunction "2_2") (pintype "passive"))
      (node (ref "TP4") (pin "1") (pintype "passive"))
    )
    (net (code "33") (name "VCC") (class "Default")
      (node (ref "F1") (pin "1") (pinfunction "1_1") (pintype "passive"))
      (node (ref "P2") (pin "1") (pinfunction "1_1") (pintype "passive"))
    )
    (net (code "34") (name "unconnected-(U1-3V3-Pad17)") (class "Default")
      (node (ref "U1") (pin "17") (pinfunction "3V3_17") (pintype "passive"))
    )
    (net (code "35") (name "unconnected-(U1-A6-Pad25)") (class "Default")
      (node (ref "U1") (pin "25") (pinfunction "A6_25") (pintype "passive"))
    )
    (net (code "36") (name "unconnected-(U1-A7-Pad26)") (class "Default")
      (node (ref "U1") (pin "26") (pinfunction "A7_26") (pintype "passive"))
    )
    (net (code "37") (name "unconnected-(U1-AREF-Pad18)") (class "Default")
      (node (ref "U1") (pin "18") (pinfunction "AREF_18") (pintype "passive"))
    )
    (net (code "38") (name "unconnected-(U1-D2{slash}PD2-Pad5)") (class "Default")
      (node (ref "U1") (pin "5") (pinfunction "D2/PD2_5") (pintype "passive"))
    )
    (net (code "39") (name "unconnected-(U1-D7{slash}PD7-Pad10)") (class "Default")
      (node (ref "U1") (pin "10") (pinfunction "D7/PD7_10") (pintype "passive"))
    )
    (net (code "40") (name "unconnected-(U1-D12{slash}PB4-Pad15)") (class "Default")
      (node (ref "U1") (pin "15") (pinfunction "D12/PB4_15") (pintype "passive"))
    )
    (net (code "41") (name "unconnected-(U1-D13{slash}PB5-Pad16)") (class "Default")
      (node (ref "U1") (pin "16") (pinfunction "D13/PB5_16") (pintype "passive"))
    )
    (net (code "42") (name "unconnected-(U1-PC3{slash}A3-Pad22)") (class "Default")
      (node (ref "U1") (pin "22") (pinfunction "PC3/A3_22") (pintype "passive"))
    )
    (net (code "43") (name "unconnected-(U1-PC4{slash}A4-Pad23)") (class "Default")
      (node (ref "U1") (pin "23") (pinfunction "PC4/A4_23") (pintype "passive"))
    )
    (net (code "44") (name "unconnected-(U1-PC5{slash}A5-Pad24)") (class "Default")
      (node (ref "U1") (pin "24") (pinfunction "PC5/A5_24") (pintype "passive"))
    )
    (net (code "45") (name "unconnected-(U1-PC6{slash}RESET-Pad28)") (class "Default")
      (node (ref "U1") (pin "28") (pinfunction "PC6/RESET_28") (pintype "passive"))
    )
    (net (code "46") (name "unconnected-(U1-RESET{slash}PC6-Pad3)") (class "Default")
      (node (ref "U1") (pin "3") (pinfunction "RESET/PC6_3") (pintype "passive"))
    )
    (net (code "47") (name "unconnected-(U1-RX-Pad2)") (class "Default")
      (node (ref "U1") (pin "2") (pinfunction "RX_2") (pintype "passive"))
    )
    (net (code "48") (name "unconnected-(U1-TX-Pad1)") (class "Default")
      (node (ref "U1") (pin "1") (pinfunction "TX_1") (pintype "passive"))
    )
    (net (code "49") (name "unconnected-(U1-VIN-Pad30)") (class "Default")
      (node (ref "U1") (pin "30") (pinfunction "VIN_30") (pintype "passive"))
    )
  )
)
